# WeMos_relay.net
KiCad netlist of a schematic drawn in EAGLE
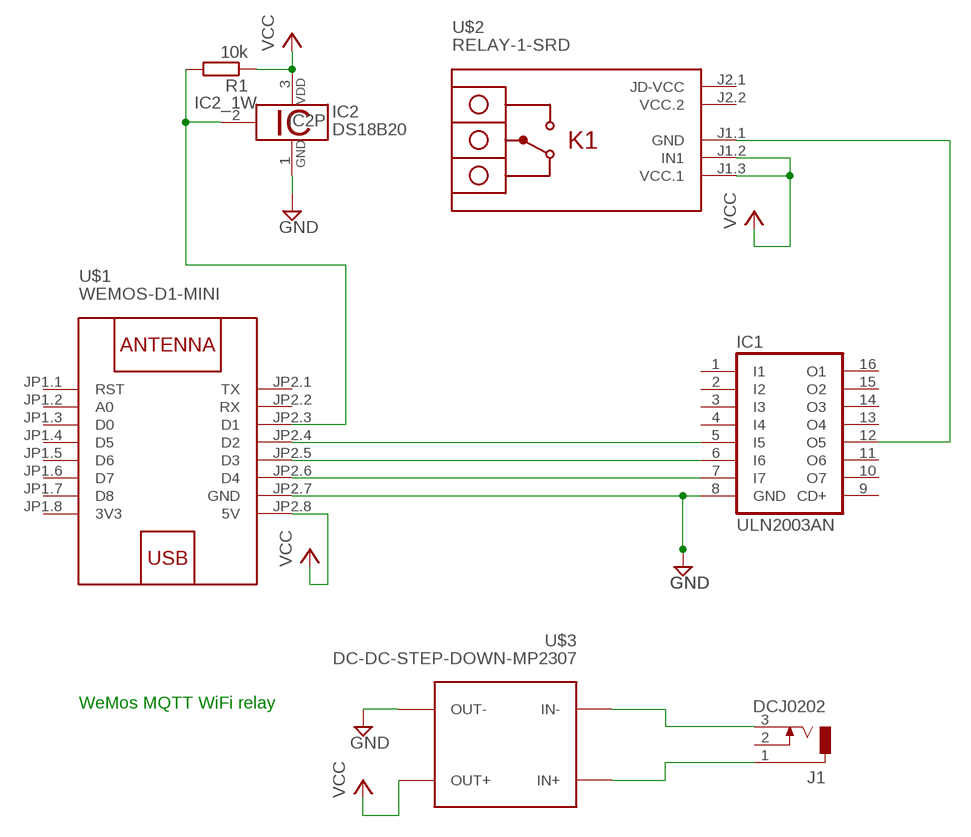
[diagram p0: schematic, sheet 1]

(export (version "E")
  (design (tool "Eeschema 10.0.6"))
  (components
    (comp (ref "IC1")
      (value "ULN2003AN")
      (footprint "eagle-import:DIL16")
      (libsource (lib "eagle-import") (part "ULN2003AN"))
    )
    (comp (ref "IC2")
      (value "DS18B20")
      (footprint "eagle-import:TO92-")
      (libsource (lib "eagle-import") (part "DS18B20"))
    )
    (comp (ref "J1")
      (value "DCJ0202")
      (footprint "eagle-import:DCJ0202")
      (libsource (lib "eagle-import") (part "DCJ0202"))
    )
    (comp (ref "R1")
      (value "10k")
      (footprint "eagle-import:0204V")
      (libsource (lib "eagle-import") (part "R-EU_0204/2V"))
    )
    (comp (ref "U$1")
      (value "WEMOS-D1-MINI")
      (footprint "eagle-import:WEMOS-D1-MINI")
      (libsource (lib "eagle-import") (part "WEMOS-D1-MINI"))
    )
    (comp (ref "U$2")
      (value "RELAY-1-SRD")
      (footprint "eagle-import:RELAY-1-SRD")
      (libsource (lib "eagle-import") (part "RELAY-1-SRD"))
    )
    (comp (ref "U$3")
      (value "DC-DC-STEP-DOWN-MP2307")
      (footprint "eagle-import:DC-DC-STEP-DOWN-MP2307")
      (libsource (lib "eagle-import") (part "DC-DC-STEP-DOWN-MP2307"))
    )
  )
  (nets
    (net (code "1") (name "/3V3") (class "Default")
      (node (ref "U$1") (pin "JP1.8") (pinfunction "3V3_JP1.8") (pintype "power_in"))
    )
    (net (code "2") (name "/VCC.2") (class "Default")
      (node (ref "U$2") (pin "J2.2") (pinfunction "VCC.2_J2.2") (pintype "power_in"))
    )
    (net (code "3") (name "GND") (class "Default")
      (node (ref "IC1") (pin "8") (pinfunction "GND_8") (pintype "power_in"))
      (node (ref "IC2") (pin "1") (pinfunction "GND_1") (pintype "power_in"))
      (node (ref "U$1") (pin "JP2.7") (pinfunction "GND_JP2.7") (pintype "power_in"))
      (node (ref "U$3") (pin "OUT-") (pinfunction "OUT-_OUT-") (pintype "bidirectional"))
    )
    (net (code "4") (name "Net-(IC1-I5)") (class "Default")
      (node (ref "IC1") (pin "5") (pinfunction "I5_5") (pintype "input"))
      (node (ref "U$1") (pin "JP2.4") (pinfunction "D2_JP2.4") (pintype "bidirectional"))
    )
    (net (code "5") (name "Net-(IC1-I6)") (class "Default")
      (node (ref "IC1") (pin "6") (pinfunction "I6_6") (pintype "input"))
      (node (ref "U$1") (pin "JP2.5") (pinfunction "D3_JP2.5") (pintype "bidirectional"))
    )
    (net (code "6") (name "Net-(IC1-I7)") (class "Default")
      (node (ref "IC1") (pin "7") (pinfunction "I7_7") (pintype "input"))
      (node (ref "U$1") (pin "JP2.6") (pinfunction "D4_JP2.6") (pintype "bidirectional"))
    )
    (net (code "7") (name "Net-(IC1-O5)") (class "Default")
      (node (ref "IC1") (pin "12") (pinfunction "O5_12") (pintype "open_collector"))
      (node (ref "U$2") (pin "J1.1") (pinfunction "GND_J1.1") (pintype "power_in"))
    )
    (net (code "8") (name "Net-(IC2C-1W)") (class "Default")
      (node (ref "IC2") (pin "2") (pinfunction "1W_2") (pintype "power_in"))
      (node (ref "R1") (pin "2") (pinfunction "2_2") (pintype "passive"))
      (node (ref "U$1") (pin "JP2.3") (pinfunction "D1_JP2.3") (pintype "bidirectional"))
    )
    (net (code "9") (name "Net-(J1-Pad1)") (class "Default")
      (node (ref "J1") (pin "1") (pinfunction "1_1") (pintype "passive"))
      (node (ref "U$3") (pin "IN+") (pinfunction "IN+_IN+") (pintype "bidirectional"))
    )
    (net (code "10") (name "Net-(J1-Pad3)") (class "Default")
      (node (ref "J1") (pin "3") (pinfunction "3_3") (pintype "passive"))
      (node (ref "U$3") (pin "IN-") (pinfunction "IN-_IN-") (pintype "bidirectional"))
    )
    (net (code "11") (name "VCC") (class "Default")
      (node (ref "IC2") (pin "3") (pinfunction "VDD_3") (pintype "power_in"))
      (node (ref "R1") (pin "1") (pinfunction "1_1") (pintype "passive"))
      (node (ref "U$1") (pin "JP2.8") (pinfunction "5V_JP2.8") (pintype "power_in"))
      (node (ref "U$2") (pin "J1.2") (pinfunction "IN1_J1.2") (pintype "bidirectional"))
      (node (ref "U$2") (pin "J1.3") (pinfunction "VCC.1_J1.3") (pintype "power_in"))
      (node (ref "U$3") (pin "OUT+") (pinfunction "OUT+_OUT+") (pintype "bidirectional"))
    )
    (net (code "12") (name "unconnected-(IC1-CD+-Pad9)") (class "Default")
      (node (ref "IC1") (pin "9") (pinfunction "CD+_9") (pintype "passive"))
    )
    (net (code "13") (name "unconnected-(IC1-I1-Pad1)") (class "Default")
      (node (ref "IC1") (pin "1") (pinfunction "I1_1") (pintype "input"))
    )
    (net (code "14") (name "unconnected-(IC1-I2-Pad2)") (class "Default")
      (node (ref "IC1") (pin "2") (pinfunction "I2_2") (pintype "input"))
    )
    (net (code "15") (name "unconnected-(IC1-I3-Pad3)") (class "Default")
      (node (ref "IC1") (pin "3") (pinfunction "I3_3") (pintype "input"))
    )
    (net (code "16") (name "unconnected-(IC1-I4-Pad4)") (class "Default")
      (node (ref "IC1") (pin "4") (pinfunction "I4_4") (pintype "input"))
    )
    (net (code "17") (name "unconnected-(IC1-O1-Pad16)") (class "Default")
      (node (ref "IC1") (pin "16") (pinfunction "O1_16") (pintype "open_collector"))
    )
    (net (code "18") (name "unconnected-(IC1-O2-Pad15)") (class "Default")
      (node (ref "IC1") (pin "15") (pinfunction "O2_15") (pintype "open_collector"))
    )
    (net (code "19") (name "unconnected-(IC1-O3-Pad14)") (class "Default")
      (node (ref "IC1") (pin "14") (pinfunction "O3_14") (pintype "open_collector"))
    )
    (net (code "20") (name "unconnected-(IC1-O4-Pad13)") (class "Default")
      (node (ref "IC1") (pin "13") (pinfunction "O4_13") (pintype "open_collector"))
    )
    (net (code "21") (name "unconnected-(IC1-O6-Pad11)") (class "Default")
      (node (ref "IC1") (pin "11") (pinfunction "O6_11") (pintype "open_collector"))
    )
    (net (code "22") (name "unconnected-(IC1-O7-Pad10)") (class "Default")
      (node (ref "IC1") (pin "10") (pinfunction "O7_10") (pintype "open_collector"))
    )
    (net (code "23") (name "unconnected-(J1-Pad2)") (class "Default")
      (node (ref "J1") (pin "2") (pinfunction "2_2") (pintype "passive"))
    )
    (net (code "24") (name "unconnected-(U$1-A0-PadJP1.2)") (class "Default")
      (node (ref "U$1") (pin "JP1.2") (pinfunction "A0_JP1.2") (pintype "bidirectional"))
    )
    (net (code "25") (name "unconnected-(U$1-D0-PadJP1.3)") (class "Default")
      (node (ref "U$1") (pin "JP1.3") (pinfunction "D0_JP1.3") (pintype "bidirectional"))
    )
    (net (code "26") (name "unconnected-(U$1-D5-PadJP1.4)") (class "Default")
      (node (ref "U$1") (pin "JP1.4") (pinfunction "D5_JP1.4") (pintype "bidirectional"))
    )
    (net (code "27") (name "unconnected-(U$1-D6-PadJP1.5)") (class "Default")
      (node (ref "U$1") (pin "JP1.5") (pinfunction "D6_JP1.5") (pintype "bidirectional"))
    )
    (net (code "28") (name "unconnected-(U$1-D7-PadJP1.6)") (class "Default")
      (node (ref "U$1") (pin "JP1.6") (pinfunction "D7_JP1.6") (pintype "bidirectional"))
    )
    (net (code "29") (name "unconnected-(U$1-D8-PadJP1.7)") (class "Default")
      (node (ref "U$1") (pin "JP1.7") (pinfunction "D8_JP1.7") (pintype "bidirectional"))
    )
    (net (code "30") (name "unconnected-(U$1-RST-PadJP1.1)") (class "Default")
      (node (ref "U$1") (pin "JP1.1") (pinfunction "RST_JP1.1") (pintype "bidirectional"))
    )
    (net (code "31") (name "unconnected-(U$1-RX-PadJP2.2)") (class "Default")
      (node (ref "U$1") (pin "JP2.2") (pinfunction "RX_JP2.2") (pintype "bidirectional"))
    )
    (net (code "32") (name "unconnected-(U$1-TX-PadJP2.1)") (class "Default")
      (node (ref "U$1") (pin "JP2.1") (pinfunction "TX_JP2.1") (pintype "bidirectional"))
    )
    (net (code "33") (name "unconnected-(U$2-JD-VCC-PadJ2.1)") (class "Default")
      (node (ref "U$2") (pin "J2.1") (pinfunction "JD-VCC_J2.1") (pintype "bidirectional"))
    )
  )
)
